# phoneline_fixer.net
KiCad netlist of a schematic drawn in EAGLE
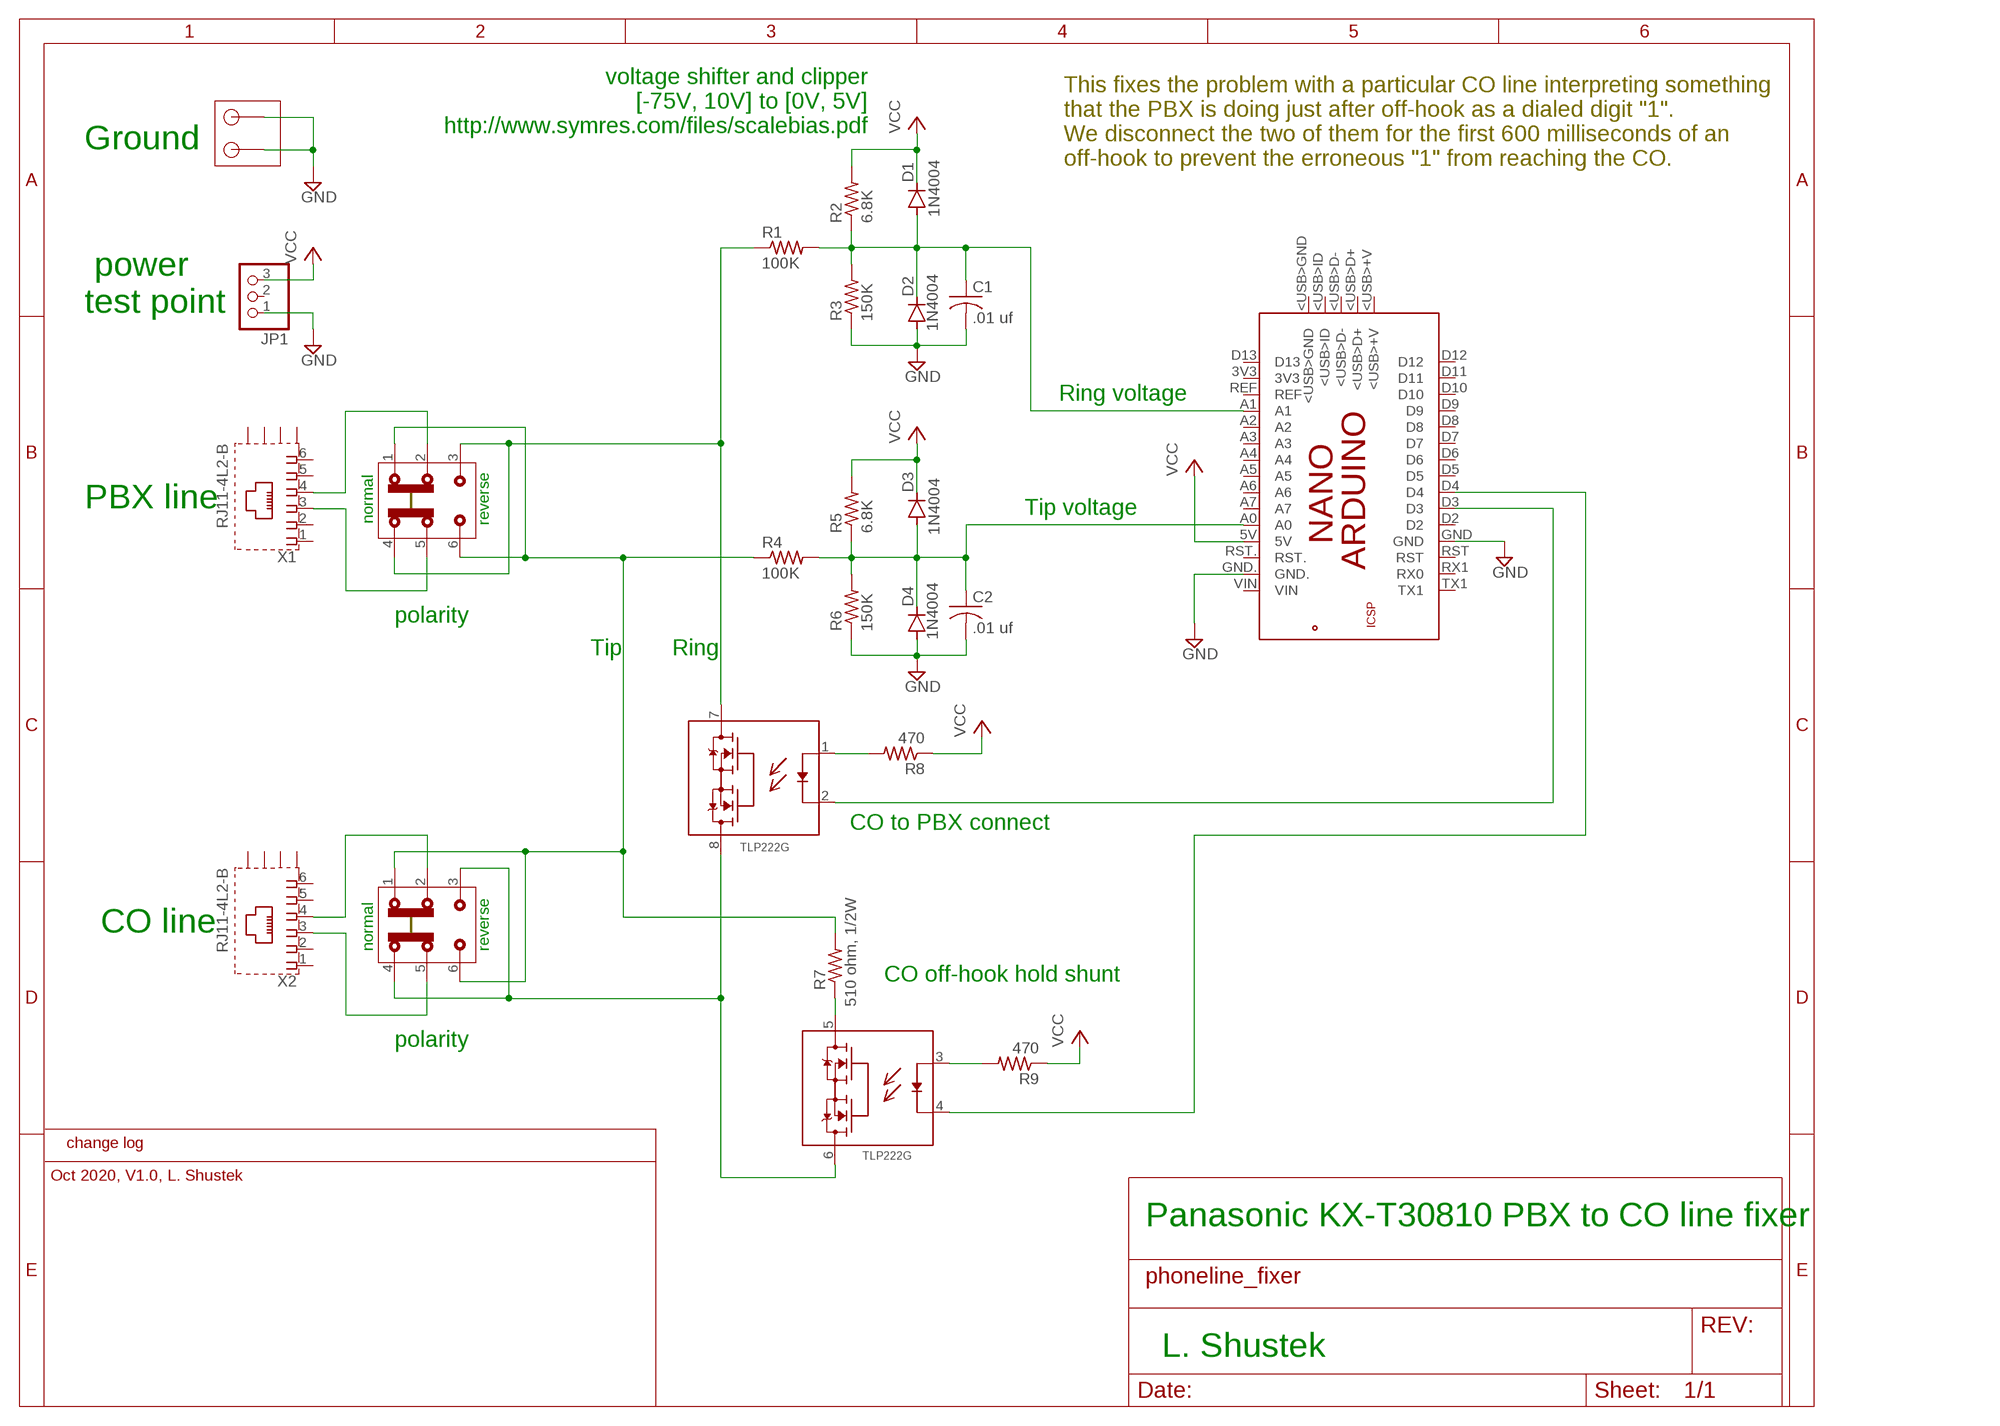
[diagram p0: schematic, sheet 1]

(export (version "E")
  (design (tool "Eeschema 10.0.6"))
  (components
    (comp (ref "C1")
      (value ".01 uf")
      (footprint "eagle-import:C050-025X075")
      (libsource (lib "eagle-import") (part "C-US050-025X075"))
    )
    (comp (ref "C2")
      (value ".01 uf")
      (footprint "eagle-import:C050-025X075")
      (libsource (lib "eagle-import") (part "C-US050-025X075"))
    )
    (comp (ref "D1")
      (value "1N4004")
      (footprint "eagle-import:DO41-10")
      (libsource (lib "eagle-import") (part "1N4004"))
    )
    (comp (ref "D2")
      (value "1N4004")
      (footprint "eagle-import:DO41-10")
      (libsource (lib "eagle-import") (part "1N4004"))
    )
    (comp (ref "D3")
      (value "1N4004")
      (footprint "eagle-import:DO41-10")
      (libsource (lib "eagle-import") (part "1N4004"))
    )
    (comp (ref "D4")
      (value "1N4004")
      (footprint "eagle-import:DO41-10")
      (libsource (lib "eagle-import") (part "1N4004"))
    )
    (comp (ref "JP1")
      (value "PINHD-1X3")
      (footprint "eagle-import:1X03")
      (libsource (lib "eagle-import") (part "PINHD-1X3"))
    )
    (comp (ref "PCB1")
      (value "ARDUINO_NANO")
      (footprint "eagle-import:ARDUINO_NANO")
      (libsource (lib "eagle-import") (part "ARDUINO_NANO"))
    )
    (comp (ref "R1")
      (value "100K")
      (footprint "eagle-import:0207_12")
      (libsource (lib "eagle-import") (part "R-US_0207/12"))
    )
    (comp (ref "R2")
      (value "6.8K")
      (footprint "eagle-import:0207_12")
      (libsource (lib "eagle-import") (part "R-US_0207/12"))
    )
    (comp (ref "R3")
      (value "150K")
      (footprint "eagle-import:0207_12")
      (libsource (lib "eagle-import") (part "R-US_0207/12"))
    )
    (comp (ref "R4")
      (value "100K")
      (footprint "eagle-import:0207_12")
      (libsource (lib "eagle-import") (part "R-US_0207/12"))
    )
    (comp (ref "R5")
      (value "6.8K")
      (footprint "eagle-import:0207_12")
      (libsource (lib "eagle-import") (part "R-US_0207/12"))
    )
    (comp (ref "R6")
      (value "150K")
      (footprint "eagle-import:0207_12")
      (libsource (lib "eagle-import") (part "R-US_0207/12"))
    )
    (comp (ref "R7")
      (value "510 ohm, 1/2W")
      (footprint "eagle-import:0414_15")
      (libsource (lib "eagle-import") (part "R-US_0414/15"))
    )
    (comp (ref "R8")
      (value "470")
      (footprint "eagle-import:0207_12")
      (libsource (lib "eagle-import") (part "R-US_0207/12"))
    )
    (comp (ref "R9")
      (value "470")
      (footprint "eagle-import:0207_12")
      (libsource (lib "eagle-import") (part "R-US_0207/12"))
    )
    (comp (ref "U$1")
      (value "TLP222G")
      (footprint "eagle-import:DIL08")
      (libsource (lib "eagle-import") (part "PHOTORELAY"))
    )
    (comp (ref "U$2")
      (value "CONNECTOR-2PINTHIN")
      (footprint "eagle-import:CONNECTOR-2PIN-5MM_THIN")
      (libsource (lib "eagle-import") (part "CONNECTOR-2PINTHIN"))
    )
    (comp (ref "U$3")
      (value "SWITCH_SLIDE_DPDT")
      (footprint "eagle-import:SWITCH_SLIDE_DPDT")
      (libsource (lib "eagle-import") (part "SWITCH_SLIDE_DPDT"))
    )
    (comp (ref "U$4")
      (value "SWITCH_SLIDE_DPDT")
      (footprint "eagle-import:SWITCH_SLIDE_DPDT")
      (libsource (lib "eagle-import") (part "SWITCH_SLIDE_DPDT"))
    )
    (comp (ref "X1")
      (value "RJ11-4L2-B")
      (footprint "eagle-import:RJ11-SHIELD2")
      (fields (field (name "MF") "TYCO ELECTRONICS"))
      (libsource (lib "eagle-import") (part "RJ112-B-4L"))
    )
    (comp (ref "X2")
      (value "RJ11-4L2-B")
      (footprint "eagle-import:RJ11-SHIELD2")
      (fields (field (name "MF") "TYCO ELECTRONICS"))
      (libsource (lib "eagle-import") (part "RJ112-B-4L"))
    )
  )
  (nets
    (net (code "1") (name "GND") (class "Default")
      (node (ref "C1") (pin "2") (pinfunction "2_2") (pintype "passive"))
      (node (ref "C2") (pin "2") (pinfunction "2_2") (pintype "passive"))
      (node (ref "D2") (pin "A") (pinfunction "A_A") (pintype "passive"))
      (node (ref "D4") (pin "A") (pinfunction "A_A") (pintype "passive"))
      (node (ref "JP1") (pin "1") (pinfunction "1_1") (pintype "passive"))
      (node (ref "PCB1") (pin "GND") (pinfunction "GND_GND") (pintype "bidirectional"))
      (node (ref "PCB1") (pin "GND.") (pinfunction "GND._GND.") (pintype "bidirectional"))
      (node (ref "R3") (pin "1") (pinfunction "1_1") (pintype "passive"))
      (node (ref "R6") (pin "1") (pinfunction "1_1") (pintype "passive"))
      (node (ref "U$2") (pin "P$1") (pinfunction "P$1_P$1") (pintype "bidirectional"))
      (node (ref "U$2") (pin "P$2") (pinfunction "P$2_P$2") (pintype "bidirectional"))
    )
    (net (code "2") (name "Net-(C1-Pad1)") (class "Default")
      (node (ref "C1") (pin "1") (pinfunction "1_1") (pintype "passive"))
      (node (ref "D1") (pin "A") (pinfunction "A_A") (pintype "passive"))
      (node (ref "D2") (pin "C") (pinfunction "C_C") (pintype "passive"))
      (node (ref "PCB1") (pin "A1") (pinfunction "A1_A1") (pintype "bidirectional"))
      (node (ref "R1") (pin "2") (pinfunction "2_2") (pintype "passive"))
      (node (ref "R2") (pin "1") (pinfunction "1_1") (pintype "passive"))
      (node (ref "R3") (pin "2") (pinfunction "2_2") (pintype "passive"))
    )
    (net (code "3") (name "Net-(C2-Pad1)") (class "Default")
      (node (ref "C2") (pin "1") (pinfunction "1_1") (pintype "passive"))
      (node (ref "D3") (pin "A") (pinfunction "A_A") (pintype "passive"))
      (node (ref "D4") (pin "C") (pinfunction "C_C") (pintype "passive"))
      (node (ref "PCB1") (pin "A0") (pinfunction "A0_A0") (pintype "bidirectional"))
      (node (ref "R4") (pin "2") (pinfunction "2_2") (pintype "passive"))
      (node (ref "R5") (pin "1") (pinfunction "1_1") (pintype "passive"))
      (node (ref "R6") (pin "2") (pinfunction "2_2") (pintype "passive"))
    )
    (net (code "4") (name "Net-(R4-Pad1)") (class "Default")
      (node (ref "R4") (pin "1") (pinfunction "1_1") (pintype "passive"))
      (node (ref "R7") (pin "2") (pinfunction "2_2") (pintype "passive"))
      (node (ref "U$3") (pin "1") (pinfunction "1_1") (pintype "bidirectional"))
      (node (ref "U$3") (pin "6") (pinfunction "6_6") (pintype "bidirectional"))
      (node (ref "U$4") (pin "1") (pinfunction "1_1") (pintype "bidirectional"))
      (node (ref "U$4") (pin "6") (pinfunction "6_6") (pintype "bidirectional"))
    )
    (net (code "5") (name "Net-(U$1A-A)") (class "Default")
      (node (ref "R8") (pin "2") (pinfunction "2_2") (pintype "passive"))
      (node (ref "U$1") (pin "1") (pinfunction "A_1") (pintype "bidirectional"))
    )
    (net (code "6") (name "Net-(U$1A-C)") (class "Default")
      (node (ref "PCB1") (pin "D3") (pinfunction "D3_D3") (pintype "bidirectional"))
      (node (ref "U$1") (pin "2") (pinfunction "C_2") (pintype "bidirectional"))
    )
    (net (code "7") (name "Net-(U$1A-D1)") (class "Default")
      (node (ref "U$1") (pin "6") (pinfunction "D1_6") (pintype "bidirectional"))
      (node (ref "U$1") (pin "8") (pinfunction "D1_8") (pintype "bidirectional"))
      (node (ref "U$4") (pin "3") (pinfunction "3_3") (pintype "bidirectional"))
      (node (ref "U$4") (pin "4") (pinfunction "4_4") (pintype "bidirectional"))
    )
    (net (code "8") (name "Net-(U$1A-D2)") (class "Default")
      (node (ref "R1") (pin "1") (pinfunction "1_1") (pintype "passive"))
      (node (ref "U$1") (pin "7") (pinfunction "D2_7") (pintype "bidirectional"))
      (node (ref "U$3") (pin "3") (pinfunction "3_3") (pintype "bidirectional"))
      (node (ref "U$3") (pin "4") (pinfunction "4_4") (pintype "bidirectional"))
    )
    (net (code "9") (name "Net-(U$1B-A)") (class "Default")
      (node (ref "R9") (pin "2") (pinfunction "2_2") (pintype "passive"))
      (node (ref "U$1") (pin "3") (pinfunction "A_3") (pintype "bidirectional"))
    )
    (net (code "10") (name "Net-(U$1B-C)") (class "Default")
      (node (ref "PCB1") (pin "D4") (pinfunction "D4_D4") (pintype "bidirectional"))
      (node (ref "U$1") (pin "4") (pinfunction "C_4") (pintype "bidirectional"))
    )
    (net (code "11") (name "Net-(U$1B-D2)") (class "Default")
      (node (ref "R7") (pin "1") (pinfunction "1_1") (pintype "passive"))
      (node (ref "U$1") (pin "5") (pinfunction "D2_5") (pintype "bidirectional"))
    )
    (net (code "12") (name "Net-(U$3-Pad2)") (class "Default")
      (node (ref "U$3") (pin "2") (pinfunction "2_2") (pintype "bidirectional"))
      (node (ref "X1") (pin "4") (pinfunction "4_4") (pintype "passive"))
    )
    (net (code "13") (name "Net-(U$3-Pad5)") (class "Default")
      (node (ref "U$3") (pin "5") (pinfunction "5_5") (pintype "bidirectional"))
      (node (ref "X1") (pin "3") (pinfunction "3_3") (pintype "passive"))
    )
    (net (code "14") (name "Net-(U$4-Pad2)") (class "Default")
      (node (ref "U$4") (pin "2") (pinfunction "2_2") (pintype "bidirectional"))
      (node (ref "X2") (pin "4") (pinfunction "4_4") (pintype "passive"))
    )
    (net (code "15") (name "Net-(U$4-Pad5)") (class "Default")
      (node (ref "U$4") (pin "5") (pinfunction "5_5") (pintype "bidirectional"))
      (node (ref "X2") (pin "3") (pinfunction "3_3") (pintype "passive"))
    )
    (net (code "16") (name "VCC") (class "Default")
      (node (ref "D1") (pin "C") (pinfunction "C_C") (pintype "passive"))
      (node (ref "D3") (pin "C") (pinfunction "C_C") (pintype "passive"))
      (node (ref "JP1") (pin "3") (pinfunction "3_3") (pintype "passive"))
      (node (ref "PCB1") (pin "5V") (pinfunction "5V_5V") (pintype "bidirectional"))
      (node (ref "R2") (pin "2") (pinfunction "2_2") (pintype "passive"))
      (node (ref "R5") (pin "2") (pinfunction "2_2") (pintype "passive"))
      (node (ref "R8") (pin "1") (pinfunction "1_1") (pintype "passive"))
      (node (ref "R9") (pin "1") (pinfunction "1_1") (pintype "passive"))
    )
    (net (code "17") (name "unconnected-(JP1-Pad2)") (class "Default")
      (node (ref "JP1") (pin "2") (pinfunction "2_2") (pintype "passive"))
    )
    (net (code "18") (name "unconnected-(PCB1-Pad3V3)") (class "Default")
      (node (ref "PCB1") (pin "3V3") (pinfunction "3V3_3V3") (pintype "bidirectional"))
    )
    (net (code "19") (name "unconnected-(PCB1-Pad5V.)") (class "Default")
      (node (ref "PCB1") (pin "5V.") (pinfunction "5V._5V.") (pintype "bidirectional"))
    )
    (net (code "20") (name "unconnected-(PCB1-Pad<USB>+V)") (class "Default")
      (node (ref "PCB1") (pin "<USB>+V") (pinfunction "<USB>+V_<USB>+V") (pintype "bidirectional"))
    )
    (net (code "21") (name "unconnected-(PCB1-Pad<USB>D+)") (class "Default")
      (node (ref "PCB1") (pin "<USB>D+") (pinfunction "<USB>D+_<USB>D+") (pintype "bidirectional"))
    )
    (net (code "22") (name "unconnected-(PCB1-Pad<USB>D-)") (class "Default")
      (node (ref "PCB1") (pin "<USB>D-") (pinfunction "<USB>D-_<USB>D-") (pintype "bidirectional"))
    )
    (net (code "23") (name "unconnected-(PCB1-Pad<USB>GND)") (class "Default")
      (node (ref "PCB1") (pin "<USB>GND") (pinfunction "<USB>GND_<USB>GND") (pintype "bidirectional"))
    )
    (net (code "24") (name "unconnected-(PCB1-Pad<USB>ID)") (class "Default")
      (node (ref "PCB1") (pin "<USB>ID") (pinfunction "<USB>ID_<USB>ID") (pintype "bidirectional"))
    )
    (net (code "25") (name "unconnected-(PCB1-PadA2)") (class "Default")
      (node (ref "PCB1") (pin "A2") (pinfunction "A2_A2") (pintype "bidirectional"))
    )
    (net (code "26") (name "unconnected-(PCB1-PadA3)") (class "Default")
      (node (ref "PCB1") (pin "A3") (pinfunction "A3_A3") (pintype "bidirectional"))
    )
    (net (code "27") (name "unconnected-(PCB1-PadA4)") (class "Default")
      (node (ref "PCB1") (pin "A4") (pinfunction "A4_A4") (pintype "bidirectional"))
    )
    (net (code "28") (name "unconnected-(PCB1-PadA5)") (class "Default")
      (node (ref "PCB1") (pin "A5") (pinfunction "A5_A5") (pintype "bidirectional"))
    )
    (net (code "29") (name "unconnected-(PCB1-PadA6)") (class "Default")
      (node (ref "PCB1") (pin "A6") (pinfunction "A6_A6") (pintype "bidirectional"))
    )
    (net (code "30") (name "unconnected-(PCB1-PadA7)") (class "Default")
      (node (ref "PCB1") (pin "A7") (pinfunction "A7_A7") (pintype "bidirectional"))
    )
    (net (code "31") (name "unconnected-(PCB1-PadD2)") (class "Default")
      (node (ref "PCB1") (pin "D2") (pinfunction "D2_D2") (pintype "bidirectional"))
    )
    (net (code "32") (name "unconnected-(PCB1-PadD5)") (class "Default")
      (node (ref "PCB1") (pin "D5") (pinfunction "D5_D5") (pintype "bidirectional"))
    )
    (net (code "33") (name "unconnected-(PCB1-PadD6)") (class "Default")
      (node (ref "PCB1") (pin "D6") (pinfunction "D6_D6") (pintype "bidirectional"))
    )
    (net (code "34") (name "unconnected-(PCB1-PadD7)") (class "Default")
      (node (ref "PCB1") (pin "D7") (pinfunction "D7_D7") (pintype "bidirectional"))
    )
    (net (code "35") (name "unconnected-(PCB1-PadD8)") (class "Default")
      (node (ref "PCB1") (pin "D8") (pinfunction "D8_D8") (pintype "bidirectional"))
    )
    (net (code "36") (name "unconnected-(PCB1-PadD9)") (class "Default")
      (node (ref "PCB1") (pin "D9") (pinfunction "D9_D9") (pintype "bidirectional"))
    )
    (net (code "37") (name "unconnected-(PCB1-PadD10)") (class "Default")
      (node (ref "PCB1") (pin "D10") (pinfunction "D10_D10") (pintype "bidirectional"))
    )
    (net (code "38") (name "unconnected-(PCB1-PadD11)") (class "Default")
      (node (ref "PCB1") (pin "D11") (pinfunction "D11_D11") (pintype "bidirectional"))
    )
    (net (code "39") (name "unconnected-(PCB1-PadD12)") (class "Default")
      (node (ref "PCB1") (pin "D12") (pinfunction "D12_D12") (pintype "bidirectional"))
    )
    (net (code "40") (name "unconnected-(PCB1-PadD13)") (class "Default")
      (node (ref "PCB1") (pin "D13") (pinfunction "D13_D13") (pintype "bidirectional"))
    )
    (net (code "41") (name "unconnected-(PCB1-PadGND_)") (class "Default")
      (node (ref "PCB1") (pin "GND_") (pinfunction "GND__GND_") (pintype "bidirectional"))
    )
    (net (code "42") (name "unconnected-(PCB1-PadMISO)") (class "Default")
      (node (ref "PCB1") (pin "MISO") (pinfunction "MISO_MISO") (pintype "bidirectional"))
    )
    (net (code "43") (name "unconnected-(PCB1-PadMOSI)") (class "Default")
      (node (ref "PCB1") (pin "MOSI") (pinfunction "MOSI_MOSI") (pintype "bidirectional"))
    )
    (net (code "44") (name "unconnected-(PCB1-PadREF)") (class "Default")
      (node (ref "PCB1") (pin "REF") (pinfunction "REF_REF") (pintype "bidirectional"))
    )
    (net (code "45") (name "unconnected-(PCB1-PadRESET..)") (class "Default")
      (node (ref "PCB1") (pin "RESET..") (pinfunction "RESET.._RESET..") (pintype "bidirectional"))
    )
    (net (code "46") (name "unconnected-(PCB1-PadRST)") (class "Default")
      (node (ref "PCB1") (pin "RST") (pinfunction "RST_RST") (pintype "bidirectional"))
    )
    (net (code "47") (name "unconnected-(PCB1-PadRST.)") (class "Default")
      (node (ref "PCB1") (pin "RST.") (pinfunction "RST._RST.") (pintype "bidirectional"))
    )
    (net (code "48") (name "unconnected-(PCB1-PadSCK)") (class "Default")
      (node (ref "PCB1") (pin "SCK") (pinfunction "SCK_SCK") (pintype "bidirectional"))
    )
    (net (code "49") (name "unconnected-(PCB1-PadTX1)") (class "Default")
      (node (ref "PCB1") (pin "TX1") (pinfunction "TX1_TX1") (pintype "bidirectional"))
    )
    (net (code "50") (name "unconnected-(PCB1-PadVIN)") (class "Default")
      (node (ref "PCB1") (pin "VIN") (pinfunction "VIN_VIN") (pintype "bidirectional"))
    )
    (net (code "51") (name "unconnected-(PCB1-RX0-PadRX1)") (class "Default")
      (node (ref "PCB1") (pin "RX1") (pinfunction "RX0_RX1") (pintype "bidirectional"))
    )
    (net (code "52") (name "unconnected-(X1-Pad1)") (class "Default")
      (node (ref "X1") (pin "1") (pinfunction "1_1") (pintype "passive"))
    )
    (net (code "53") (name "unconnected-(X1-Pad2)") (class "Default")
      (node (ref "X1") (pin "2") (pinfunction "2_2") (pintype "passive"))
    )
    (net (code "54") (name "unconnected-(X1-Pad5)") (class "Default")
      (node (ref "X1") (pin "5") (pinfunction "5_5") (pintype "passive"))
    )
    (net (code "55") (name "unconnected-(X1-Pad6)") (class "Default")
      (node (ref "X1") (pin "6") (pinfunction "6_6") (pintype "passive"))
    )
    (net (code "56") (name "unconnected-(X1-S-PadS1)") (class "Default")
      (node (ref "X1") (pin "S1") (pinfunction "S_S1") (pintype "passive"))
    )
    (net (code "57") (name "unconnected-(X1-S-PadS2)") (class "Default")
      (node (ref "X1") (pin "S2") (pinfunction "S_S2") (pintype "passive"))
    )
    (net (code "58") (name "unconnected-(X1-S-PadS3)") (class "Default")
      (node (ref "X1") (pin "S3") (pinfunction "S_S3") (pintype "passive"))
    )
    (net (code "59") (name "unconnected-(X1-S-PadS4)") (class "Default")
      (node (ref "X1") (pin "S4") (pinfunction "S_S4") (pintype "passive"))
    )
    (net (code "60") (name "unconnected-(X2-Pad1)") (class "Default")
      (node (ref "X2") (pin "1") (pinfunction "1_1") (pintype "passive"))
    )
    (net (code "61") (name "unconnected-(X2-Pad2)") (class "Default")
      (node (ref "X2") (pin "2") (pinfunction "2_2") (pintype "passive"))
    )
    (net (code "62") (name "unconnected-(X2-Pad5)") (class "Default")
      (node (ref "X2") (pin "5") (pinfunction "5_5") (pintype "passive"))
    )
    (net (code "63") (name "unconnected-(X2-Pad6)") (class "Default")
      (node (ref "X2") (pin "6") (pinfunction "6_6") (pintype "passive"))
    )
    (net (code "64") (name "unconnected-(X2-S-PadS1)") (class "Default")
      (node (ref "X2") (pin "S1") (pinfunction "S_S1") (pintype "passive"))
    )
    (net (code "65") (name "unconnected-(X2-S-PadS2)") (class "Default")
      (node (ref "X2") (pin "S2") (pinfunction "S_S2") (pintype "passive"))
    )
    (net (code "66") (name "unconnected-(X2-S-PadS3)") (class "Default")
      (node (ref "X2") (pin "S3") (pinfunction "S_S3") (pintype "passive"))
    )
    (net (code "67") (name "unconnected-(X2-S-PadS4)") (class "Default")
      (node (ref "X2") (pin "S4") (pinfunction "S_S4") (pintype "passive"))
    )
  )
)
